# Solenoise_v5.net
KiCad netlist of a schematic drawn in EAGLE
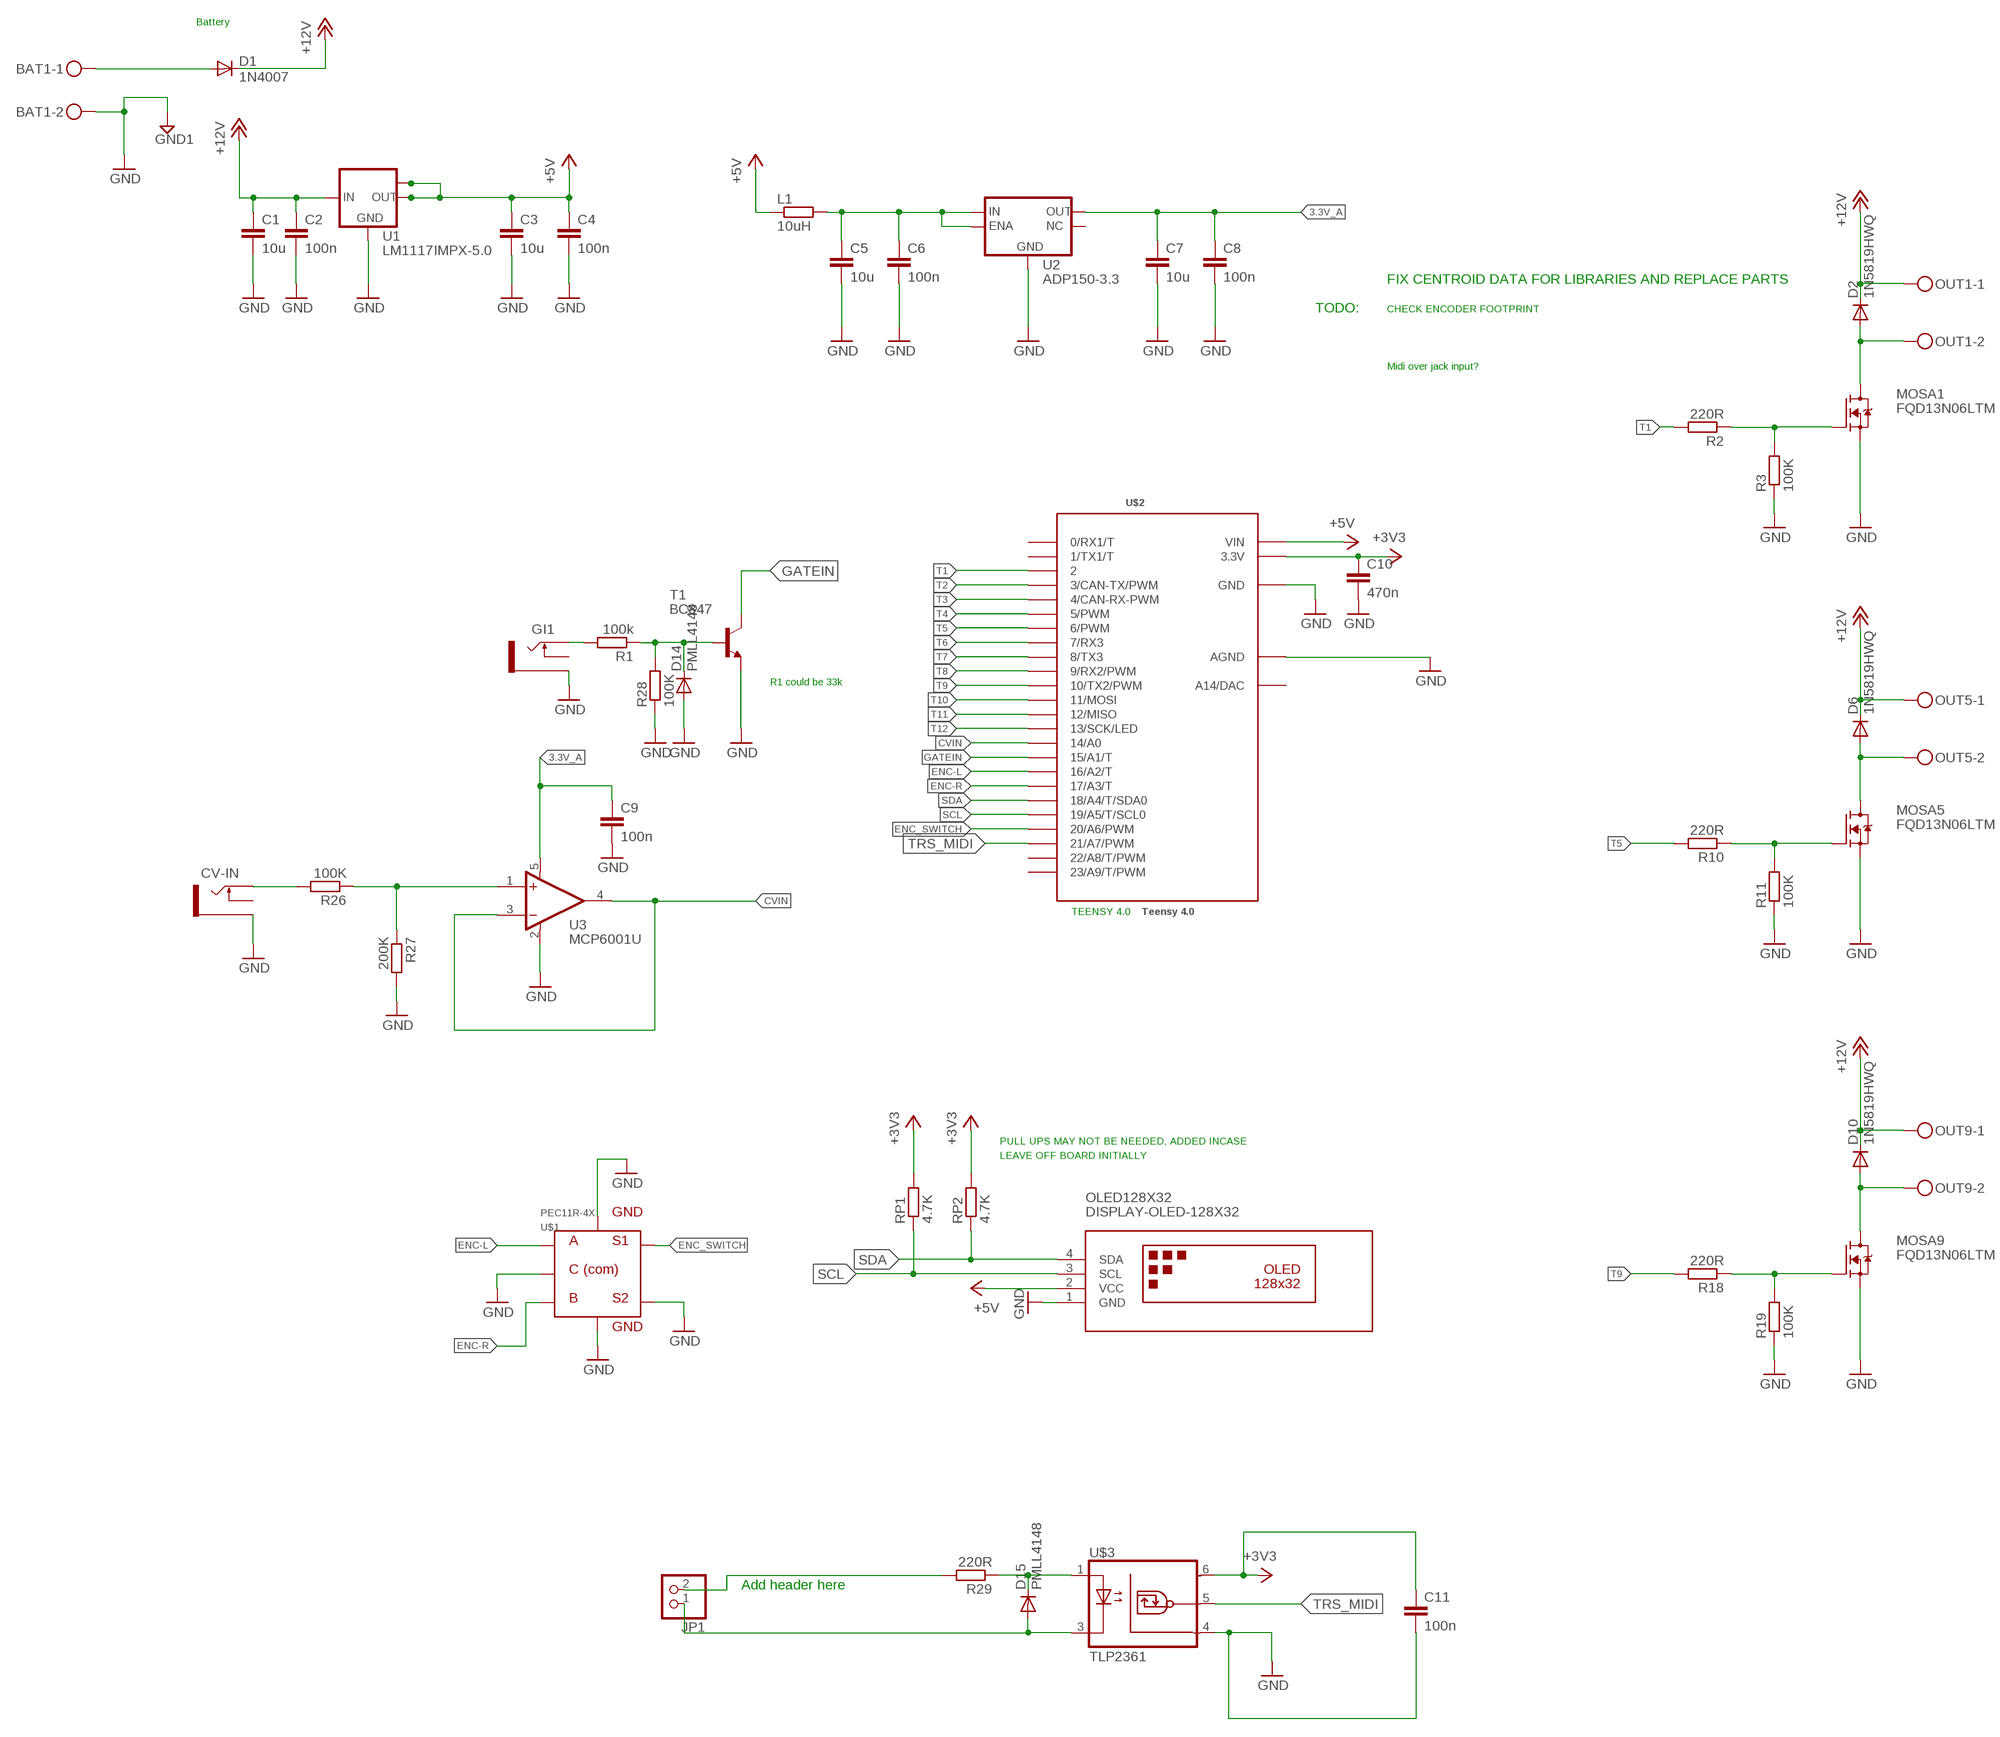
[diagram p0: schematic, sheet 1, part 1 of 2]
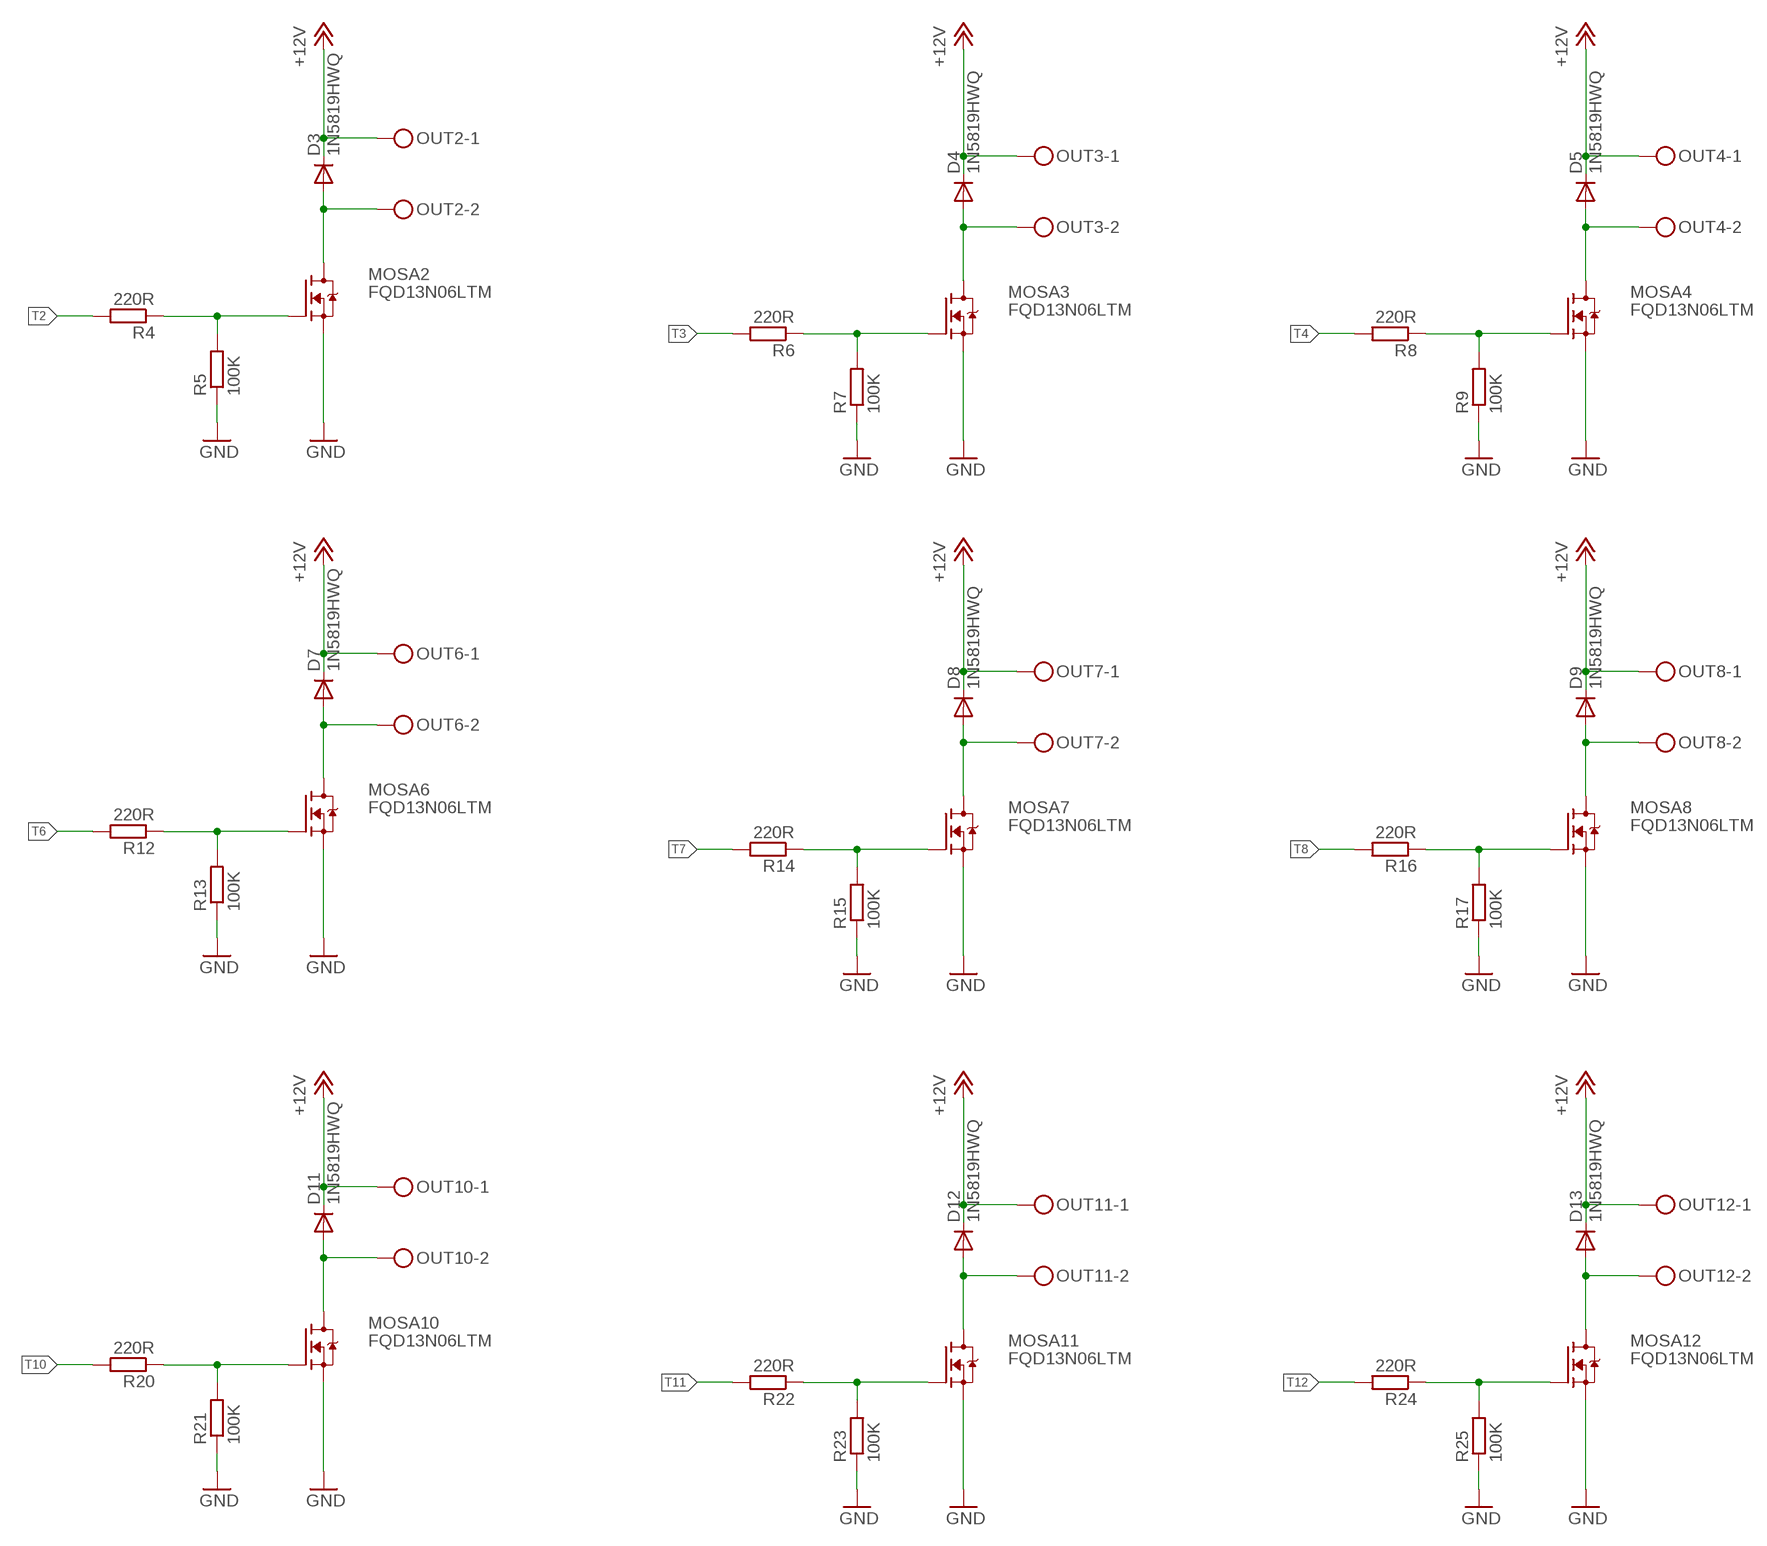
[diagram p1: schematic, sheet 1, part 2 of 2]

(export (version "E")
  (design (tool "Eeschema 10.0.6"))
  (components
    (comp (ref "BAT1")
      (value "MKDSN1,5/2-5,08")
      (footprint "eagle-import:MKDSN1,5_2-5,08")
      (fields (field (name "MPN") "MKDSN 1,5/2-5.08"))
      (libsource (lib "eagle-import") (part "MKDSN1,5/2-5,08"))
    )
    (comp (ref "C1")
      (value "10u")
      (footprint "eagle-import:C1206")
      (libsource (lib "eagle-import") (part "C-EUC1206"))
    )
    (comp (ref "C2")
      (value "100n")
      (footprint "eagle-import:C0805")
      (libsource (lib "eagle-import") (part "C-EUC0805"))
    )
    (comp (ref "C3")
      (value "10u")
      (footprint "eagle-import:C1206")
      (libsource (lib "eagle-import") (part "C-EUC1206"))
    )
    (comp (ref "C4")
      (value "100n")
      (footprint "eagle-import:C0805")
      (libsource (lib "eagle-import") (part "C-EUC0805"))
    )
    (comp (ref "C5")
      (value "10u")
      (footprint "eagle-import:C1206")
      (libsource (lib "eagle-import") (part "C-EUC1206"))
    )
    (comp (ref "C6")
      (value "100n")
      (footprint "eagle-import:C0805")
      (libsource (lib "eagle-import") (part "C-EUC0805"))
    )
    (comp (ref "C7")
      (value "10u")
      (footprint "eagle-import:C1206")
      (libsource (lib "eagle-import") (part "C-EUC1206"))
    )
    (comp (ref "C8")
      (value "100n")
      (footprint "eagle-import:C0805")
      (libsource (lib "eagle-import") (part "C-EUC0805"))
    )
    (comp (ref "C9")
      (value "100n")
      (footprint "eagle-import:C0805")
      (libsource (lib "eagle-import") (part "C-EUC0805"))
    )
    (comp (ref "C10")
      (value "470n")
      (footprint "eagle-import:C0805")
      (libsource (lib "eagle-import") (part "C-EUC0805"))
    )
    (comp (ref "C11")
      (value "100n")
      (footprint "eagle-import:C0805")
      (libsource (lib "eagle-import") (part "C-EUC0805"))
    )
    (comp (ref "CV-IN")
      (value "THONKICONNNEW")
      (footprint "eagle-import:WQP-PJ301M-12_JACK")
      (libsource (lib "eagle-import") (part "THONKICONNNEW"))
    )
    (comp (ref "D1")
      (value "1N4007")
      (footprint "eagle-import:DO41-10")
      (libsource (lib "eagle-import") (part "1N4004"))
    )
    (comp (ref "D2")
      (value "1N5819HWQ")
      (footprint "eagle-import:SOD123")
      (libsource (lib "eagle-import") (part "MBR0520LT"))
    )
    (comp (ref "D3")
      (value "1N5819HWQ")
      (footprint "eagle-import:SOD123")
      (libsource (lib "eagle-import") (part "MBR0520LT"))
    )
    (comp (ref "D4")
      (value "1N5819HWQ")
      (footprint "eagle-import:SOD123")
      (libsource (lib "eagle-import") (part "MBR0520LT"))
    )
    (comp (ref "D5")
      (value "1N5819HWQ")
      (footprint "eagle-import:SOD123")
      (libsource (lib "eagle-import") (part "MBR0520LT"))
    )
    (comp (ref "D6")
      (value "1N5819HWQ")
      (footprint "eagle-import:SOD123")
      (libsource (lib "eagle-import") (part "MBR0520LT"))
    )
    (comp (ref "D7")
      (value "1N5819HWQ")
      (footprint "eagle-import:SOD123")
      (libsource (lib "eagle-import") (part "MBR0520LT"))
    )
    (comp (ref "D8")
      (value "1N5819HWQ")
      (footprint "eagle-import:SOD123")
      (libsource (lib "eagle-import") (part "MBR0520LT"))
    )
    (comp (ref "D9")
      (value "1N5819HWQ")
      (footprint "eagle-import:SOD123")
      (libsource (lib "eagle-import") (part "MBR0520LT"))
    )
    (comp (ref "D10")
      (value "1N5819HWQ")
      (footprint "eagle-import:SOD123")
      (libsource (lib "eagle-import") (part "MBR0520LT"))
    )
    (comp (ref "D11")
      (value "1N5819HWQ")
      (footprint "eagle-import:SOD123")
      (libsource (lib "eagle-import") (part "MBR0520LT"))
    )
    (comp (ref "D12")
      (value "1N5819HWQ")
      (footprint "eagle-import:SOD123")
      (libsource (lib "eagle-import") (part "MBR0520LT"))
    )
    (comp (ref "D13")
      (value "1N5819HWQ")
      (footprint "eagle-import:SOD123")
      (libsource (lib "eagle-import") (part "MBR0520LT"))
    )
    (comp (ref "D14")
      (value "PMLL4148")
      (footprint "eagle-import:SOD80C")
      (libsource (lib "eagle-import") (part "PMLL4150"))
    )
    (comp (ref "D15")
      (value "PMLL4148")
      (footprint "eagle-import:SOD80C")
      (libsource (lib "eagle-import") (part "PMLL4150"))
    )
    (comp (ref "GI1")
      (value "THONKICONNNEW")
      (footprint "eagle-import:WQP-PJ301M-12_JACK")
      (libsource (lib "eagle-import") (part "THONKICONNNEW"))
    )
    (comp (ref "JP1")
      (value "PINHD-1X2")
      (footprint "eagle-import:1X02")
      (libsource (lib "eagle-import") (part "PINHD-1X2"))
    )
    (comp (ref "L1")
      (value "10uH")
      (footprint "eagle-import:R0805")
      (libsource (lib "eagle-import") (part "R-EU_R0805"))
    )
    (comp (ref "MOSA1")
      (value "FQD13N06LTM")
      (footprint "eagle-import:FQD13N06LTM")
      (libsource (lib "eagle-import") (part "FQD13N06LTM"))
    )
    (comp (ref "MOSA2")
      (value "FQD13N06LTM")
      (footprint "eagle-import:FQD13N06LTM")
      (libsource (lib "eagle-import") (part "FQD13N06LTM"))
    )
    (comp (ref "MOSA3")
      (value "FQD13N06LTM")
      (footprint "eagle-import:FQD13N06LTM")
      (libsource (lib "eagle-import") (part "FQD13N06LTM"))
    )
    (comp (ref "MOSA4")
      (value "FQD13N06LTM")
      (footprint "eagle-import:FQD13N06LTM")
      (libsource (lib "eagle-import") (part "FQD13N06LTM"))
    )
    (comp (ref "MOSA5")
      (value "FQD13N06LTM")
      (footprint "eagle-import:FQD13N06LTM")
      (libsource (lib "eagle-import") (part "FQD13N06LTM"))
    )
    (comp (ref "MOSA6")
      (value "FQD13N06LTM")
      (footprint "eagle-import:FQD13N06LTM")
      (libsource (lib "eagle-import") (part "FQD13N06LTM"))
    )
    (comp (ref "MOSA7")
      (value "FQD13N06LTM")
      (footprint "eagle-import:FQD13N06LTM")
      (libsource (lib "eagle-import") (part "FQD13N06LTM"))
    )
    (comp (ref "MOSA8")
      (value "FQD13N06LTM")
      (footprint "eagle-import:FQD13N06LTM")
      (libsource (lib "eagle-import") (part "FQD13N06LTM"))
    )
    (comp (ref "MOSA9")
      (value "FQD13N06LTM")
      (footprint "eagle-import:FQD13N06LTM")
      (libsource (lib "eagle-import") (part "FQD13N06LTM"))
    )
    (comp (ref "MOSA10")
      (value "FQD13N06LTM")
      (footprint "eagle-import:FQD13N06LTM")
      (libsource (lib "eagle-import") (part "FQD13N06LTM"))
    )
    (comp (ref "MOSA11")
      (value "FQD13N06LTM")
      (footprint "eagle-import:FQD13N06LTM")
      (libsource (lib "eagle-import") (part "FQD13N06LTM"))
    )
    (comp (ref "MOSA12")
      (value "FQD13N06LTM")
      (footprint "eagle-import:FQD13N06LTM")
      (libsource (lib "eagle-import") (part "FQD13N06LTM"))
    )
    (comp (ref "OLED128X32")
      (value "DISPLAY-OLED-128X32")
      (footprint "eagle-import:DISPLAY-OLED-128X32")
      (libsource (lib "eagle-import") (part "DISPLAY-OLED-128X32"))
    )
    (comp (ref "OUT1")
      (value "MKDSN1,5/2-5,08")
      (footprint "eagle-import:MKDSN1,5_2-5,08")
      (fields (field (name "MPN") "MKDSN 1,5/2-5.08"))
      (libsource (lib "eagle-import") (part "MKDSN1,5/2-5,08"))
    )
    (comp (ref "OUT2")
      (value "MKDSN1,5/2-5,08")
      (footprint "eagle-import:MKDSN1,5_2-5,08")
      (fields (field (name "MPN") "MKDSN 1,5/2-5.08"))
      (libsource (lib "eagle-import") (part "MKDSN1,5/2-5,08"))
    )
    (comp (ref "OUT3")
      (value "MKDSN1,5/2-5,08")
      (footprint "eagle-import:MKDSN1,5_2-5,08")
      (fields (field (name "MPN") "MKDSN 1,5/2-5.08"))
      (libsource (lib "eagle-import") (part "MKDSN1,5/2-5,08"))
    )
    (comp (ref "OUT4")
      (value "MKDSN1,5/2-5,08")
      (footprint "eagle-import:MKDSN1,5_2-5,08")
      (fields (field (name "MPN") "MKDSN 1,5/2-5.08"))
      (libsource (lib "eagle-import") (part "MKDSN1,5/2-5,08"))
    )
    (comp (ref "OUT5")
      (value "MKDSN1,5/2-5,08")
      (footprint "eagle-import:MKDSN1,5_2-5,08")
      (fields (field (name "MPN") "MKDSN 1,5/2-5.08"))
      (libsource (lib "eagle-import") (part "MKDSN1,5/2-5,08"))
    )
    (comp (ref "OUT6")
      (value "MKDSN1,5/2-5,08")
      (footprint "eagle-import:MKDSN1,5_2-5,08")
      (fields (field (name "MPN") "MKDSN 1,5/2-5.08"))
      (libsource (lib "eagle-import") (part "MKDSN1,5/2-5,08"))
    )
    (comp (ref "OUT7")
      (value "MKDSN1,5/2-5,08")
      (footprint "eagle-import:MKDSN1,5_2-5,08")
      (fields (field (name "MPN") "MKDSN 1,5/2-5.08"))
      (libsource (lib "eagle-import") (part "MKDSN1,5/2-5,08"))
    )
    (comp (ref "OUT8")
      (value "MKDSN1,5/2-5,08")
      (footprint "eagle-import:MKDSN1,5_2-5,08")
      (fields (field (name "MPN") "MKDSN 1,5/2-5.08"))
      (libsource (lib "eagle-import") (part "MKDSN1,5/2-5,08"))
    )
    (comp (ref "OUT9")
      (value "MKDSN1,5/2-5,08")
      (footprint "eagle-import:MKDSN1,5_2-5,08")
      (fields (field (name "MPN") "MKDSN 1,5/2-5.08"))
      (libsource (lib "eagle-import") (part "MKDSN1,5/2-5,08"))
    )
    (comp (ref "OUT10")
      (value "MKDSN1,5/2-5,08")
      (footprint "eagle-import:MKDSN1,5_2-5,08")
      (fields (field (name "MPN") "MKDSN 1,5/2-5.08"))
      (libsource (lib "eagle-import") (part "MKDSN1,5/2-5,08"))
    )
    (comp (ref "OUT11")
      (value "MKDSN1,5/2-5,08")
      (footprint "eagle-import:MKDSN1,5_2-5,08")
      (fields (field (name "MPN") "MKDSN 1,5/2-5.08"))
      (libsource (lib "eagle-import") (part "MKDSN1,5/2-5,08"))
    )
    (comp (ref "OUT12")
      (value "MKDSN1,5/2-5,08")
      (footprint "eagle-import:MKDSN1,5_2-5,08")
      (fields (field (name "MPN") "MKDSN 1,5/2-5.08"))
      (libsource (lib "eagle-import") (part "MKDSN1,5/2-5,08"))
    )
    (comp (ref "R1")
      (value "100k")
      (footprint "eagle-import:R0805")
      (libsource (lib "eagle-import") (part "R-EU_R0805"))
    )
    (comp (ref "R2")
      (value "220R")
      (footprint "eagle-import:R0805")
      (libsource (lib "eagle-import") (part "R-EU_R0805"))
    )
    (comp (ref "R3")
      (value "100K")
      (footprint "eagle-import:R0805")
      (libsource (lib "eagle-import") (part "R-EU_R0805"))
    )
    (comp (ref "R4")
      (value "220R")
      (footprint "eagle-import:R0805")
      (libsource (lib "eagle-import") (part "R-EU_R0805"))
    )
    (comp (ref "R5")
      (value "100K")
      (footprint "eagle-import:R0805")
      (libsource (lib "eagle-import") (part "R-EU_R0805"))
    )
    (comp (ref "R6")
      (value "220R")
      (footprint "eagle-import:R0805")
      (libsource (lib "eagle-import") (part "R-EU_R0805"))
    )
    (comp (ref "R7")
      (value "100K")
      (footprint "eagle-import:R0805")
      (libsource (lib "eagle-import") (part "R-EU_R0805"))
    )
    (comp (ref "R8")
      (value "220R")
      (footprint "eagle-import:R0805")
      (libsource (lib "eagle-import") (part "R-EU_R0805"))
    )
    (comp (ref "R9")
      (value "100K")
      (footprint "eagle-import:R0805")
      (libsource (lib "eagle-import") (part "R-EU_R0805"))
    )
    (comp (ref "R10")
      (value "220R")
      (footprint "eagle-import:R0805")
      (libsource (lib "eagle-import") (part "R-EU_R0805"))
    )
    (comp (ref "R11")
      (value "100K")
      (footprint "eagle-import:R0805")
      (libsource (lib "eagle-import") (part "R-EU_R0805"))
    )
    (comp (ref "R12")
      (value "220R")
      (footprint "eagle-import:R0805")
      (libsource (lib "eagle-import") (part "R-EU_R0805"))
    )
    (comp (ref "R13")
      (value "100K")
      (footprint "eagle-import:R0805")
      (libsource (lib "eagle-import") (part "R-EU_R0805"))
    )
    (comp (ref "R14")
      (value "220R")
      (footprint "eagle-import:R0805")
      (libsource (lib "eagle-import") (part "R-EU_R0805"))
    )
    (comp (ref "R15")
      (value "100K")
      (footprint "eagle-import:R0805")
      (libsource (lib "eagle-import") (part "R-EU_R0805"))
    )
    (comp (ref "R16")
      (value "220R")
      (footprint "eagle-import:R0805")
      (libsource (lib "eagle-import") (part "R-EU_R0805"))
    )
    (comp (ref "R17")
      (value "100K")
      (footprint "eagle-import:R0805")
      (libsource (lib "eagle-import") (part "R-EU_R0805"))
    )
    (comp (ref "R18")
      (value "220R")
      (footprint "eagle-import:R0805")
      (libsource (lib "eagle-import") (part "R-EU_R0805"))
    )
    (comp (ref "R19")
      (value "100K")
      (footprint "eagle-import:R0805")
      (libsource (lib "eagle-import") (part "R-EU_R0805"))
    )
    (comp (ref "R20")
      (value "220R")
      (footprint "eagle-import:R0805")
      (libsource (lib "eagle-import") (part "R-EU_R0805"))
    )
    (comp (ref "R21")
      (value "100K")
      (footprint "eagle-import:R0805")
      (libsource (lib "eagle-import") (part "R-EU_R0805"))
    )
    (comp (ref "R22")
      (value "220R")
      (footprint "eagle-import:R0805")
      (libsource (lib "eagle-import") (part "R-EU_R0805"))
    )
    (comp (ref "R23")
      (value "100K")
      (footprint "eagle-import:R0805")
      (libsource (lib "eagle-import") (part "R-EU_R0805"))
    )
    (comp (ref "R24")
      (value "220R")
      (footprint "eagle-import:R0805")
      (libsource (lib "eagle-import") (part "R-EU_R0805"))
    )
    (comp (ref "R25")
      (value "100K")
      (footprint "eagle-import:R0805")
      (libsource (lib "eagle-import") (part "R-EU_R0805"))
    )
    (comp (ref "R26")
      (value "100K")
      (footprint "eagle-import:R0805")
      (libsource (lib "eagle-import") (part "R-EU_R0805"))
    )
    (comp (ref "R27")
      (value "200K")
      (footprint "eagle-import:R0805")
      (libsource (lib "eagle-import") (part "R-EU_R0805"))
    )
    (comp (ref "R28")
      (value "100K")
      (footprint "eagle-import:R0805")
      (libsource (lib "eagle-import") (part "R-EU_R0805"))
    )
    (comp (ref "R29")
      (value "220R")
      (footprint "eagle-import:R0805")
      (libsource (lib "eagle-import") (part "R-EU_R0805"))
    )
    (comp (ref "RP1")
      (value "4.7K")
      (footprint "eagle-import:R0805")
      (libsource (lib "eagle-import") (part "R-EU_R0805"))
    )
    (comp (ref "RP2")
      (value "4.7K")
      (footprint "eagle-import:R0805")
      (libsource (lib "eagle-import") (part "R-EU_R0805"))
    )
    (comp (ref "T1")
      (value "BC847")
      (footprint "eagle-import:SOT23")
      (libsource (lib "eagle-import") (part "BC847"))
    )
    (comp (ref "U$1")
      (value "PEC11R-4X")
      (footprint "eagle-import:ENC")
      (libsource (lib "eagle-import") (part "PEC11R-4X"))
    )
    (comp (ref "U$2")
      (value "Teensy 4.0")
      (footprint "eagle-import:TEENSY_3.1_DAC")
      (libsource (lib "eagle-import") (part "TEENSY_3.1_DAC"))
    )
    (comp (ref "U$3")
      (value "TLP2361")
      (footprint "eagle-import:TLP2361")
      (libsource (lib "eagle-import") (part "TLP2361"))
    )
    (comp (ref "U1")
      (value "LM1117IMPX-5.0")
      (footprint "eagle-import:SOT223")
      (libsource (lib "eagle-import") (part "LM1117IMPX-5.0"))
    )
    (comp (ref "U2")
      (value "ADP150-3.3")
      (footprint "eagle-import:SOT23-5")
      (libsource (lib "eagle-import") (part "ADP150-3.3"))
    )
    (comp (ref "U3")
      (value "MCP6001U")
      (footprint "eagle-import:MCP6001")
      (libsource (lib "eagle-import") (part "MCP6001U"))
    )
  )
  (nets
    (net (code "1") (name "+3V3") (class "Default")
      (node (ref "C10") (pin "1") (pinfunction "1_1") (pintype "passive"))
      (node (ref "C11") (pin "1") (pinfunction "1_1") (pintype "passive"))
      (node (ref "RP1") (pin "2") (pinfunction "2_2") (pintype "passive"))
      (node (ref "RP2") (pin "2") (pinfunction "2_2") (pintype "passive"))
      (node (ref "U$2") (pin "3.3V") (pinfunction "3.3V_3.3V") (pintype "power_in"))
      (node (ref "U$3") (pin "6") (pinfunction "VCC_6") (pintype "passive"))
    )
    (net (code "2") (name "+5V") (class "Default")
      (node (ref "C3") (pin "1") (pinfunction "1_1") (pintype "passive"))
      (node (ref "C4") (pin "1") (pinfunction "1_1") (pintype "passive"))
      (node (ref "L1") (pin "1") (pinfunction "1_1") (pintype "passive"))
      (node (ref "OLED128X32") (pin "2") (pinfunction "VCC_2") (pintype "power_in"))
      (node (ref "U$2") (pin "VIN") (pinfunction "VIN_VIN") (pintype "power_in"))
      (node (ref "U1") (pin "2") (pinfunction "OUT_2") (pintype "passive"))
      (node (ref "U1") (pin "TAB") (pinfunction "OUT1_TAB") (pintype "passive"))
    )
    (net (code "3") (name "+12V") (class "Default")
      (node (ref "C1") (pin "1") (pinfunction "1_1") (pintype "passive"))
      (node (ref "C2") (pin "1") (pinfunction "1_1") (pintype "passive"))
      (node (ref "D1") (pin "C") (pinfunction "C_C") (pintype "passive"))
      (node (ref "D10") (pin "C") (pinfunction "C_C") (pintype "passive"))
      (node (ref "D11") (pin "C") (pinfunction "C_C") (pintype "passive"))
      (node (ref "D12") (pin "C") (pinfunction "C_C") (pintype "passive"))
      (node (ref "D13") (pin "C") (pinfunction "C_C") (pintype "passive"))
      (node (ref "D2") (pin "C") (pinfunction "C_C") (pintype "passive"))
      (node (ref "D3") (pin "C") (pinfunction "C_C") (pintype "passive"))
      (node (ref "D4") (pin "C") (pinfunction "C_C") (pintype "passive"))
      (node (ref "D5") (pin "C") (pinfunction "C_C") (pintype "passive"))
      (node (ref "D6") (pin "C") (pinfunction "C_C") (pintype "passive"))
      (node (ref "D7") (pin "C") (pinfunction "C_C") (pintype "passive"))
      (node (ref "D8") (pin "C") (pinfunction "C_C") (pintype "passive"))
      (node (ref "D9") (pin "C") (pinfunction "C_C") (pintype "passive"))
      (node (ref "OUT1") (pin "1") (pinfunction "KL_1") (pintype "passive"))
      (node (ref "OUT10") (pin "1") (pinfunction "KL_1") (pintype "passive"))
      (node (ref "OUT11") (pin "1") (pinfunction "KL_1") (pintype "passive"))
      (node (ref "OUT12") (pin "1") (pinfunction "KL_1") (pintype "passive"))
      (node (ref "OUT2") (pin "1") (pinfunction "KL_1") (pintype "passive"))
      (node (ref "OUT3") (pin "1") (pinfunction "KL_1") (pintype "passive"))
      (node (ref "OUT4") (pin "1") (pinfunction "KL_1") (pintype "passive"))
      (node (ref "OUT5") (pin "1") (pinfunction "KL_1") (pintype "passive"))
      (node (ref "OUT6") (pin "1") (pinfunction "KL_1") (pintype "passive"))
      (node (ref "OUT7") (pin "1") (pinfunction "KL_1") (pintype "passive"))
      (node (ref "OUT8") (pin "1") (pinfunction "KL_1") (pintype "passive"))
      (node (ref "OUT9") (pin "1") (pinfunction "KL_1") (pintype "passive"))
      (node (ref "U1") (pin "3") (pinfunction "IN_3") (pintype "input"))
    )
    (net (code "4") (name "3.3V_A") (class "Default")
      (node (ref "C7") (pin "1") (pinfunction "1_1") (pintype "passive"))
      (node (ref "C8") (pin "1") (pinfunction "1_1") (pintype "passive"))
      (node (ref "C9") (pin "1") (pinfunction "1_1") (pintype "passive"))
      (node (ref "U2") (pin "OUT") (pinfunction "VOUT_OUT") (pintype "passive"))
      (node (ref "U3") (pin "5") (pinfunction "V+_5") (pintype "power_in"))
    )
    (net (code "5") (name "CVIN") (class "Default")
      (node (ref "U$2") (pin "14/A0") (pinfunction "14/A0_14/A0") (pintype "bidirectional"))
      (node (ref "U3") (pin "3") (pinfunction "-IN_3") (pintype "input"))
      (node (ref "U3") (pin "4") (pinfunction "OUT_4") (pintype "output"))
    )
    (net (code "6") (name "ENC-L") (class "Default")
      (node (ref "U$1") (pin "A") (pinfunction "A_A") (pintype "passive"))
      (node (ref "U$2") (pin "16/A2") (pinfunction "16/A2/T_16/A2") (pintype "bidirectional"))
    )
    (net (code "7") (name "ENC-R") (class "Default")
      (node (ref "U$1") (pin "B") (pinfunction "B_B") (pintype "passive"))
      (node (ref "U$2") (pin "17/A3") (pinfunction "17/A3/T_17/A3") (pintype "bidirectional"))
    )
    (net (code "8") (name "ENC_SWITCH") (class "Default")
      (node (ref "U$1") (pin "1") (pinfunction "SW1_1") (pintype "passive"))
      (node (ref "U$2") (pin "20/A6") (pinfunction "20/A6/PWM_20/A6") (pintype "bidirectional"))
    )
    (net (code "9") (name "GATEIN") (class "Default")
      (node (ref "T1") (pin "3") (pinfunction "C_3") (pintype "passive"))
      (node (ref "U$2") (pin "15/A1") (pinfunction "15/A1/T_15/A1") (pintype "bidirectional"))
    )
    (net (code "10") (name "GND") (class "Default")
      (node (ref "BAT1") (pin "2") (pinfunction "KL_2") (pintype "passive"))
      (node (ref "C1") (pin "2") (pinfunction "2_2") (pintype "passive"))
      (node (ref "C10") (pin "2") (pinfunction "2_2") (pintype "passive"))
      (node (ref "C11") (pin "2") (pinfunction "2_2") (pintype "passive"))
      (node (ref "C2") (pin "2") (pinfunction "2_2") (pintype "passive"))
      (node (ref "C3") (pin "2") (pinfunction "2_2") (pintype "passive"))
      (node (ref "C4") (pin "2") (pinfunction "2_2") (pintype "passive"))
      (node (ref "C5") (pin "2") (pinfunction "2_2") (pintype "passive"))
      (node (ref "C6") (pin "2") (pinfunction "2_2") (pintype "passive"))
      (node (ref "C7") (pin "2") (pinfunction "2_2") (pintype "passive"))
      (node (ref "C8") (pin "2") (pinfunction "2_2") (pintype "passive"))
      (node (ref "C9") (pin "2") (pinfunction "2_2") (pintype "passive"))
      (node (ref "CV-IN") (pin "P$3_SLEEVE") (pinfunction "SLEEVE_P$3_SLEEVE") (pintype "passive"))
      (node (ref "D14") (pin "A") (pinfunction "A_A") (pintype "passive"))
      (node (ref "GI1") (pin "P$3_SLEEVE") (pinfunction "SLEEVE_P$3_SLEEVE") (pintype "passive"))
      (node (ref "MOSA1") (pin "2") (pinfunction "S_2") (pintype "passive"))
      (node (ref "MOSA10") (pin "2") (pinfunction "S_2") (pintype "passive"))
      (node (ref "MOSA11") (pin "2") (pinfunction "S_2") (pintype "passive"))
      (node (ref "MOSA12") (pin "2") (pinfunction "S_2") (pintype "passive"))
      (node (ref "MOSA2") (pin "2") (pinfunction "S_2") (pintype "passive"))
      (node (ref "MOSA3") (pin "2") (pinfunction "S_2") (pintype "passive"))
      (node (ref "MOSA4") (pin "2") (pinfunction "S_2") (pintype "passive"))
      (node (ref "MOSA5") (pin "2") (pinfunction "S_2") (pintype "passive"))
      (node (ref "MOSA6") (pin "2") (pinfunction "S_2") (pintype "passive"))
      (node (ref "MOSA7") (pin "2") (pinfunction "S_2") (pintype "passive"))
      (node (ref "MOSA8") (pin "2") (pinfunction "S_2") (pintype "passive"))
      (node (ref "MOSA9") (pin "2") (pinfunction "S_2") (pintype "passive"))
      (node (ref "OLED128X32") (pin "1") (pinfunction "GND_1") (pintype "power_in"))
      (node (ref "R11") (pin "1") (pinfunction "1_1") (pintype "passive"))
      (node (ref "R13") (pin "1") (pinfunction "1_1") (pintype "passive"))
      (node (ref "R15") (pin "1") (pinfunction "1_1") (pintype "passive"))
      (node (ref "R17") (pin "1") (pinfunction "1_1") (pintype "passive"))
      (node (ref "R19") (pin "1") (pinfunction "1_1") (pintype "passive"))
      (node (ref "R21") (pin "1") (pinfunction "1_1") (pintype "passive"))
      (node (ref "R23") (pin "1") (pinfunction "1_1") (pintype "passive"))
      (node (ref "R25") (pin "1") (pinfunction "1_1") (pintype "passive"))
      (node (ref "R27") (pin "2") (pinfunction "2_2") (pintype "passive"))
      (node (ref "R28") (pin "1") (pinfunction "1_1") (pintype "passive"))
      (node (ref "R3") (pin "1") (pinfunction "1_1") (pintype "passive"))
      (node (ref "R5") (pin "1") (pinfunction "1_1") (pintype "passive"))
      (node (ref "R7") (pin "1") (pinfunction "1_1") (pintype "passive"))
      (node (ref "R9") (pin "1") (pinfunction "1_1") (pintype "passive"))
      (node (ref "T1") (pin "2") (pinfunction "E_2") (pintype "passive"))
      (node (ref "U$1") (pin "2") (pinfunction "SW2_2") (pintype "passive"))
      (node (ref "U$1") (pin "C") (pinfunction "C_C") (pintype "passive"))
      (node (ref "U$1") (pin "GND1") (pinfunction "GND1_GND1") (pintype "passive"))
      (node (ref "U$1") (pin "GND2") (pinfunction "GND2_GND2") (pintype "passive"))
      (node (ref "U$2") (pin "AGND") (pinfunction "AGND_AGND") (pintype "power_in"))
      (node (ref "U$2") (pin "GND") (pinfunction "GND_GND") (pintype "power_in"))
      (node (ref "U$3") (pin "4") (pinfunction "GND_4") (pintype "passive"))
      (node (ref "U1") (pin "1") (pinfunction "GND_1") (pintype "input"))
      (node (ref "U2") (pin "GND") (pinfunction "GND_GND") (pintype "input"))
      (node (ref "U3") (pin "2") (pinfunction "V-_2") (pintype "power_in"))
    )
    (net (code "11") (name "Net-(BAT1A-KL)") (class "Default")
      (node (ref "BAT1") (pin "1") (pinfunction "KL_1") (pintype "passive"))
      (node (ref "D1") (pin "A") (pinfunction "A_A") (pintype "passive"))
    )
    (net (code "12") (name "Net-(CV-IN-TIP)") (class "Default")
      (node (ref "CV-IN") (pin "P$1_TIP") (pinfunction "TIP_P$1_TIP") (pintype "passive"))
      (node (ref "R26") (pin "2") (pinfunction "2_2") (pintype "passive"))
    )
    (net (code "13") (name "Net-(GI1-TIP)") (class "Default")
      (node (ref "GI1") (pin "P$1_TIP") (pinfunction "TIP_P$1_TIP") (pintype "passive"))
      (node (ref "R1") (pin "2") (pinfunction "2_2") (pintype "passive"))
    )
    (net (code "14") (name "Net-(JP1-Pad2)") (class "Default")
      (node (ref "JP1") (pin "2") (pinfunction "2_2") (pintype "passive"))
      (node (ref "R29") (pin "2") (pinfunction "2_2") (pintype "passive"))
    )
    (net (code "15") (name "Net-(MOSA1-D)") (class "Default")
      (node (ref "D2") (pin "A") (pinfunction "A_A") (pintype "passive"))
      (node (ref "MOSA1") (pin "3") (pinfunction "D_3") (pintype "passive"))
      (node (ref "OUT1") (pin "2") (pinfunction "KL_2") (pintype "passive"))
    )
    (net (code "16") (name "Net-(MOSA1-G)") (class "Default")
      (node (ref "MOSA1") (pin "1") (pinfunction "G_1") (pintype "passive"))
      (node (ref "R2") (pin "1") (pinfunction "1_1") (pintype "passive"))
      (node (ref "R3") (pin "2") (pinfunction "2_2") (pintype "passive"))
    )
    (net (code "17") (name "Net-(MOSA2-D)") (class "Default")
      (node (ref "D3") (pin "A") (pinfunction "A_A") (pintype "passive"))
      (node (ref "MOSA2") (pin "3") (pinfunction "D_3") (pintype "passive"))
      (node (ref "OUT2") (pin "2") (pinfunction "KL_2") (pintype "passive"))
    )
    (net (code "18") (name "Net-(MOSA2-G)") (class "Default")
      (node (ref "MOSA2") (pin "1") (pinfunction "G_1") (pintype "passive"))
      (node (ref "R4") (pin "1") (pinfunction "1_1") (pintype "passive"))
      (node (ref "R5") (pin "2") (pinfunction "2_2") (pintype "passive"))
    )
    (net (code "19") (name "Net-(MOSA3-D)") (class "Default")
      (node (ref "D4") (pin "A") (pinfunction "A_A") (pintype "passive"))
      (node (ref "MOSA3") (pin "3") (pinfunction "D_3") (pintype "passive"))
      (node (ref "OUT3") (pin "2") (pinfunction "KL_2") (pintype "passive"))
    )
    (net (code "20") (name "Net-(MOSA3-G)") (class "Default")
      (node (ref "MOSA3") (pin "1") (pinfunction "G_1") (pintype "passive"))
      (node (ref "R6") (pin "1") (pinfunction "1_1") (pintype "passive"))
      (node (ref "R7") (pin "2") (pinfunction "2_2") (pintype "passive"))
    )
    (net (code "21") (name "Net-(MOSA4-D)") (class "Default")
      (node (ref "D5") (pin "A") (pinfunction "A_A") (pintype "passive"))
      (node (ref "MOSA4") (pin "3") (pinfunction "D_3") (pintype "passive"))
      (node (ref "OUT4") (pin "2") (pinfunction "KL_2") (pintype "passive"))
    )
    (net (code "22") (name "Net-(MOSA4-G)") (class "Default")
      (node (ref "MOSA4") (pin "1") (pinfunction "G_1") (pintype "passive"))
      (node (ref "R8") (pin "1") (pinfunction "1_1") (pintype "passive"))
      (node (ref "R9") (pin "2") (pinfunction "2_2") (pintype "passive"))
    )
    (net (code "23") (name "Net-(MOSA5-D)") (class "Default")
      (node (ref "D6") (pin "A") (pinfunction "A_A") (pintype "passive"))
      (node (ref "MOSA5") (pin "3") (pinfunction "D_3") (pintype "passive"))
      (node (ref "OUT5") (pin "2") (pinfunction "KL_2") (pintype "passive"))
    )
    (net (code "24") (name "Net-(MOSA5-G)") (class "Default")
      (node (ref "MOSA5") (pin "1") (pinfunction "G_1") (pintype "passive"))
      (node (ref "R10") (pin "1") (pinfunction "1_1") (pintype "passive"))
      (node (ref "R11") (pin "2") (pinfunction "2_2") (pintype "passive"))
    )
    (net (code "25") (name "Net-(MOSA6-D)") (class "Default")
      (node (ref "D7") (pin "A") (pinfunction "A_A") (pintype "passive"))
      (node (ref "MOSA6") (pin "3") (pinfunction "D_3") (pintype "passive"))
      (node (ref "OUT6") (pin "2") (pinfunction "KL_2") (pintype "passive"))
    )
    (net (code "26") (name "Net-(MOSA6-G)") (class "Default")
      (node (ref "MOSA6") (pin "1") (pinfunction "G_1") (pintype "passive"))
      (node (ref "R12") (pin "1") (pinfunction "1_1") (pintype "passive"))
      (node (ref "R13") (pin "2") (pinfunction "2_2") (pintype "passive"))
    )
    (net (code "27") (name "Net-(MOSA7-D)") (class "Default")
      (node (ref "D8") (pin "A") (pinfunction "A_A") (pintype "passive"))
      (node (ref "MOSA7") (pin "3") (pinfunction "D_3") (pintype "passive"))
      (node (ref "OUT7") (pin "2") (pinfunction "KL_2") (pintype "passive"))
    )
    (net (code "28") (name "Net-(MOSA7-G)") (class "Default")
      (node (ref "MOSA7") (pin "1") (pinfunction "G_1") (pintype "passive"))
      (node (ref "R14") (pin "1") (pinfunction "1_1") (pintype "passive"))
      (node (ref "R15") (pin "2") (pinfunction "2_2") (pintype "passive"))
    )
    (net (code "29") (name "Net-(MOSA8-D)") (class "Default")
      (node (ref "D9") (pin "A") (pinfunction "A_A") (pintype "passive"))
      (node (ref "MOSA8") (pin "3") (pinfunction "D_3") (pintype "passive"))
      (node (ref "OUT8") (pin "2") (pinfunction "KL_2") (pintype "passive"))
    )
    (net (code "30") (name "Net-(MOSA8-G)") (class "Default")
      (node (ref "MOSA8") (pin "1") (pinfunction "G_1") (pintype "passive"))
      (node (ref "R16") (pin "1") (pinfunction "1_1") (pintype "passive"))
      (node (ref "R17") (pin "2") (pinfunction "2_2") (pintype "passive"))
    )
    (net (code "31") (name "Net-(MOSA9-D)") (class "Default")
      (node (ref "D10") (pin "A") (pinfunction "A_A") (pintype "passive"))
      (node (ref "MOSA9") (pin "3") (pinfunction "D_3") (pintype "passive"))
      (node (ref "OUT9") (pin "2") (pinfunction "KL_2") (pintype "passive"))
    )
    (net (code "32") (name "Net-(MOSA9-G)") (class "Default")
      (node (ref "MOSA9") (pin "1") (pinfunction "G_1") (pintype "passive"))
      (node (ref "R18") (pin "1") (pinfunction "1_1") (pintype "passive"))
      (node (ref "R19") (pin "2") (pinfunction "2_2") (pintype "passive"))
    )
    (net (code "33") (name "Net-(MOSA10-D)") (class "Default")
      (node (ref "D11") (pin "A") (pinfunction "A_A") (pintype "passive"))
      (node (ref "MOSA10") (pin "3") (pinfunction "D_3") (pintype "passive"))
      (node (ref "OUT10") (pin "2") (pinfunction "KL_2") (pintype "passive"))
    )
    (net (code "34") (name "Net-(MOSA10-G)") (class "Default")
      (node (ref "MOSA10") (pin "1") (pinfunction "G_1") (pintype "passive"))
      (node (ref "R20") (pin "1") (pinfunction "1_1") (pintype "passive"))
      (node (ref "R21") (pin "2") (pinfunction "2_2") (pintype "passive"))
    )
    (net (code "35") (name "Net-(MOSA11-D)") (class "Default")
      (node (ref "D12") (pin "A") (pinfunction "A_A") (pintype "passive"))
      (node (ref "MOSA11") (pin "3") (pinfunction "D_3") (pintype "passive"))
      (node (ref "OUT11") (pin "2") (pinfunction "KL_2") (pintype "passive"))
    )
    (net (code "36") (name "Net-(MOSA11-G)") (class "Default")
      (node (ref "MOSA11") (pin "1") (pinfunction "G_1") (pintype "passive"))
      (node (ref "R22") (pin "1") (pinfunction "1_1") (pintype "passive"))
      (node (ref "R23") (pin "2") (pinfunction "2_2") (pintype "passive"))
    )
    (net (code "37") (name "Net-(MOSA12-D)") (class "Default")
      (node (ref "D13") (pin "A") (pinfunction "A_A") (pintype "passive"))
      (node (ref "MOSA12") (pin "3") (pinfunction "D_3") (pintype "passive"))
      (node (ref "OUT12") (pin "2") (pinfunction "KL_2") (pintype "passive"))
    )
    (net (code "38") (name "Net-(MOSA12-G)") (class "Default")
      (node (ref "MOSA12") (pin "1") (pinfunction "G_1") (pintype "passive"))
      (node (ref "R24") (pin "1") (pinfunction "1_1") (pintype "passive"))
      (node (ref "R25") (pin "2") (pinfunction "2_2") (pintype "passive"))
    )
    (net (code "39") (name "Net-(T1-B)") (class "Default")
      (node (ref "D14") (pin "C") (pinfunction "C_C") (pintype "passive"))
      (node (ref "R1") (pin "1") (pinfunction "1_1") (pintype "passive"))
      (node (ref "R28") (pin "2") (pinfunction "2_2") (pintype "passive"))
      (node (ref "T1") (pin "1") (pinfunction "B_1") (pintype "passive"))
    )
    (net (code "40") (name "Net-(U$3-A)") (class "Default")
      (node (ref "D15") (pin "C") (pinfunction "C_C") (pintype "passive"))
      (node (ref "R29") (pin "1") (pinfunction "1_1") (pintype "passive"))
      (node (ref "U$3") (pin "1") (pinfunction "A_1") (pintype "passive"))
    )
    (net (code "41") (name "Net-(U$3-C)") (class "Default")
      (node (ref "D15") (pin "A") (pinfunction "A_A") (pintype "passive"))
      (node (ref "JP1") (pin "1") (pinfunction "1_1") (pintype "passive"))
      (node (ref "U$3") (pin "3") (pinfunction "C_3") (pintype "passive"))
    )
    (net (code "42") (name "Net-(U2-ENA)") (class "Default")
      (node (ref "C5") (pin "1") (pinfunction "1_1") (pintype "passive"))
      (node (ref "C6") (pin "1") (pinfunction "1_1") (pintype "passive"))
      (node (ref "L1") (pin "2") (pinfunction "2_2") (pintype "passive"))
      (node (ref "U2") (pin "EN") (pinfunction "ENA_EN") (pintype "input"))
      (node (ref "U2") (pin "VIN") (pinfunction "IN_VIN") (pintype "input"))
    )
    (net (code "43") (name "Net-(U3-+IN)") (class "Default")
      (node (ref "R26") (pin "1") (pinfunction "1_1") (pintype "passive"))
      (node (ref "R27") (pin "1") (pinfunction "1_1") (pintype "passive"))
      (node (ref "U3") (pin "1") (pinfunction "+IN_1") (pintype "input"))
    )
    (net (code "44") (name "SCL") (class "Default")
      (node (ref "OLED128X32") (pin "3") (pinfunction "SCL_3") (pintype "bidirectional"))
      (node (ref "RP1") (pin "1") (pinfunction "1_1") (pintype "passive"))
      (node (ref "U$2") (pin "19/A5") (pinfunction "19/A5/T/SCL0_19/A5") (pintype "bidirectional"))
    )
    (net (code "45") (name "SDA") (class "Default")
      (node (ref "OLED128X32") (pin "4") (pinfunction "SDA_4") (pintype "bidirectional"))
      (node (ref "RP2") (pin "1") (pinfunction "1_1") (pintype "passive"))
      (node (ref "U$2") (pin "18/A4") (pinfunction "18/A4/T/SDA0_18/A4") (pintype "bidirectional"))
    )
    (net (code "46") (name "T1") (class "Default")
      (node (ref "R2") (pin "2") (pinfunction "2_2") (pintype "passive"))
      (node (ref "U$2") (pin "2") (pinfunction "2_2") (pintype "bidirectional"))
    )
    (net (code "47") (name "T2") (class "Default")
      (node (ref "R4") (pin "2") (pinfunction "2_2") (pintype "passive"))
      (node (ref "U$2") (pin "3") (pinfunction "3/CAN-TX/PWM_3") (pintype "bidirectional"))
    )
    (net (code "48") (name "T3") (class "Default")
      (node (ref "R6") (pin "2") (pinfunction "2_2") (pintype "passive"))
      (node (ref "U$2") (pin "4") (pinfunction "4/CAN-RX-PWM_4") (pintype "bidirectional"))
    )
    (net (code "49") (name "T4") (class "Default")
      (node (ref "R8") (pin "2") (pinfunction "2_2") (pintype "passive"))
      (node (ref "U$2") (pin "5") (pinfunction "5/PWM_5") (pintype "bidirectional"))
    )
    (net (code "50") (name "T5") (class "Default")
      (node (ref "R10") (pin "2") (pinfunction "2_2") (pintype "passive"))
      (node (ref "U$2") (pin "6") (pinfunction "6/PWM_6") (pintype "bidirectional"))
    )
    (net (code "51") (name "T6") (class "Default")
      (node (ref "R12") (pin "2") (pinfunction "2_2") (pintype "passive"))
      (node (ref "U$2") (pin "7") (pinfunction "7/RX3_7") (pintype "bidirectional"))
    )
    (net (code "52") (name "T7") (class "Default")
      (node (ref "R14") (pin "2") (pinfunction "2_2") (pintype "passive"))
      (node (ref "U$2") (pin "8") (pinfunction "8/TX3_8") (pintype "bidirectional"))
    )
    (net (code "53") (name "T8") (class "Default")
      (node (ref "R16") (pin "2") (pinfunction "2_2") (pintype "passive"))
      (node (ref "U$2") (pin "9") (pinfunction "9/RX2/PWM_9") (pintype "bidirectional"))
    )
    (net (code "54") (name "T9") (class "Default")
      (node (ref "R18") (pin "2") (pinfunction "2_2") (pintype "passive"))
      (node (ref "U$2") (pin "10") (pinfunction "10/TX2/PWM_10") (pintype "bidirectional"))
    )
    (net (code "55") (name "T10") (class "Default")
      (node (ref "R20") (pin "2") (pinfunction "2_2") (pintype "passive"))
      (node (ref "U$2") (pin "11") (pinfunction "11/MOSI_11") (pintype "bidirectional"))
    )
    (net (code "56") (name "T11") (class "Default")
      (node (ref "R22") (pin "2") (pinfunction "2_2") (pintype "passive"))
      (node (ref "U$2") (pin "12") (pinfunction "12/MISO_12") (pintype "bidirectional"))
    )
    (net (code "57") (name "T12") (class "Default")
      (node (ref "R24") (pin "2") (pinfunction "2_2") (pintype "passive"))
      (node (ref "U$2") (pin "13") (pinfunction "13/SCK/LED_13") (pintype "bidirectional"))
    )
    (net (code "58") (name "TRS_MIDI") (class "Default")
      (node (ref "U$2") (pin "21/A7") (pinfunction "21/A7/PWM_21/A7") (pintype "bidirectional"))
      (node (ref "U$3") (pin "5") (pinfunction "VO_5") (pintype "passive"))
    )
    (net (code "59") (name "unconnected-(CV-IN-SWITCH-PadP$2_SWITCH)") (class "Default")
      (node (ref "CV-IN") (pin "P$2_SWITCH") (pinfunction "SWITCH_P$2_SWITCH") (pintype "passive"))
    )
    (net (code "60") (name "unconnected-(GI1-SWITCH-PadP$2_SWITCH)") (class "Default")
      (node (ref "GI1") (pin "P$2_SWITCH") (pinfunction "SWITCH_P$2_SWITCH") (pintype "passive"))
    )
    (net (code "61") (name "unconnected-(U$2-0{slash}RX1{slash}T-Pad0)") (class "Default")
      (node (ref "U$2") (pin "0") (pinfunction "0/RX1/T_0") (pintype "bidirectional"))
    )
    (net (code "62") (name "unconnected-(U$2-1{slash}TX1{slash}T-Pad1)") (class "Default")
      (node (ref "U$2") (pin "1") (pinfunction "1/TX1/T_1") (pintype "bidirectional"))
    )
    (net (code "63") (name "unconnected-(U$2-22{slash}A8{slash}T{slash}PWM-Pad22{slash}A8)") (class "Default")
      (node (ref "U$2") (pin "22/A8") (pinfunction "22/A8/T/PWM_22/A8") (pintype "bidirectional"))
    )
    (net (code "64") (name "unconnected-(U$2-23{slash}A9{slash}T{slash}PWM-Pad23{slash}A9)") (class "Default")
      (node (ref "U$2") (pin "23/A9") (pinfunction "23/A9/T/PWM_23/A9") (pintype "bidirectional"))
    )
    (net (code "65") (name "unconnected-(U$2-A14{slash}DAC-PadRESET{slash}DAC)") (class "Default")
      (node (ref "U$2") (pin "RESET/DAC") (pinfunction "A14/DAC_RESET/DAC") (pintype "bidirectional"))
    )
    (net (code "66") (name "unconnected-(U2-PadNC)") (class "Default")
      (node (ref "U2") (pin "NC") (pinfunction "NC_NC") (pintype "passive"))
    )
  )
)
